# ESP32_WITH_USBCV1I1.net
KiCad netlist of a schematic drawn in Altium Designer
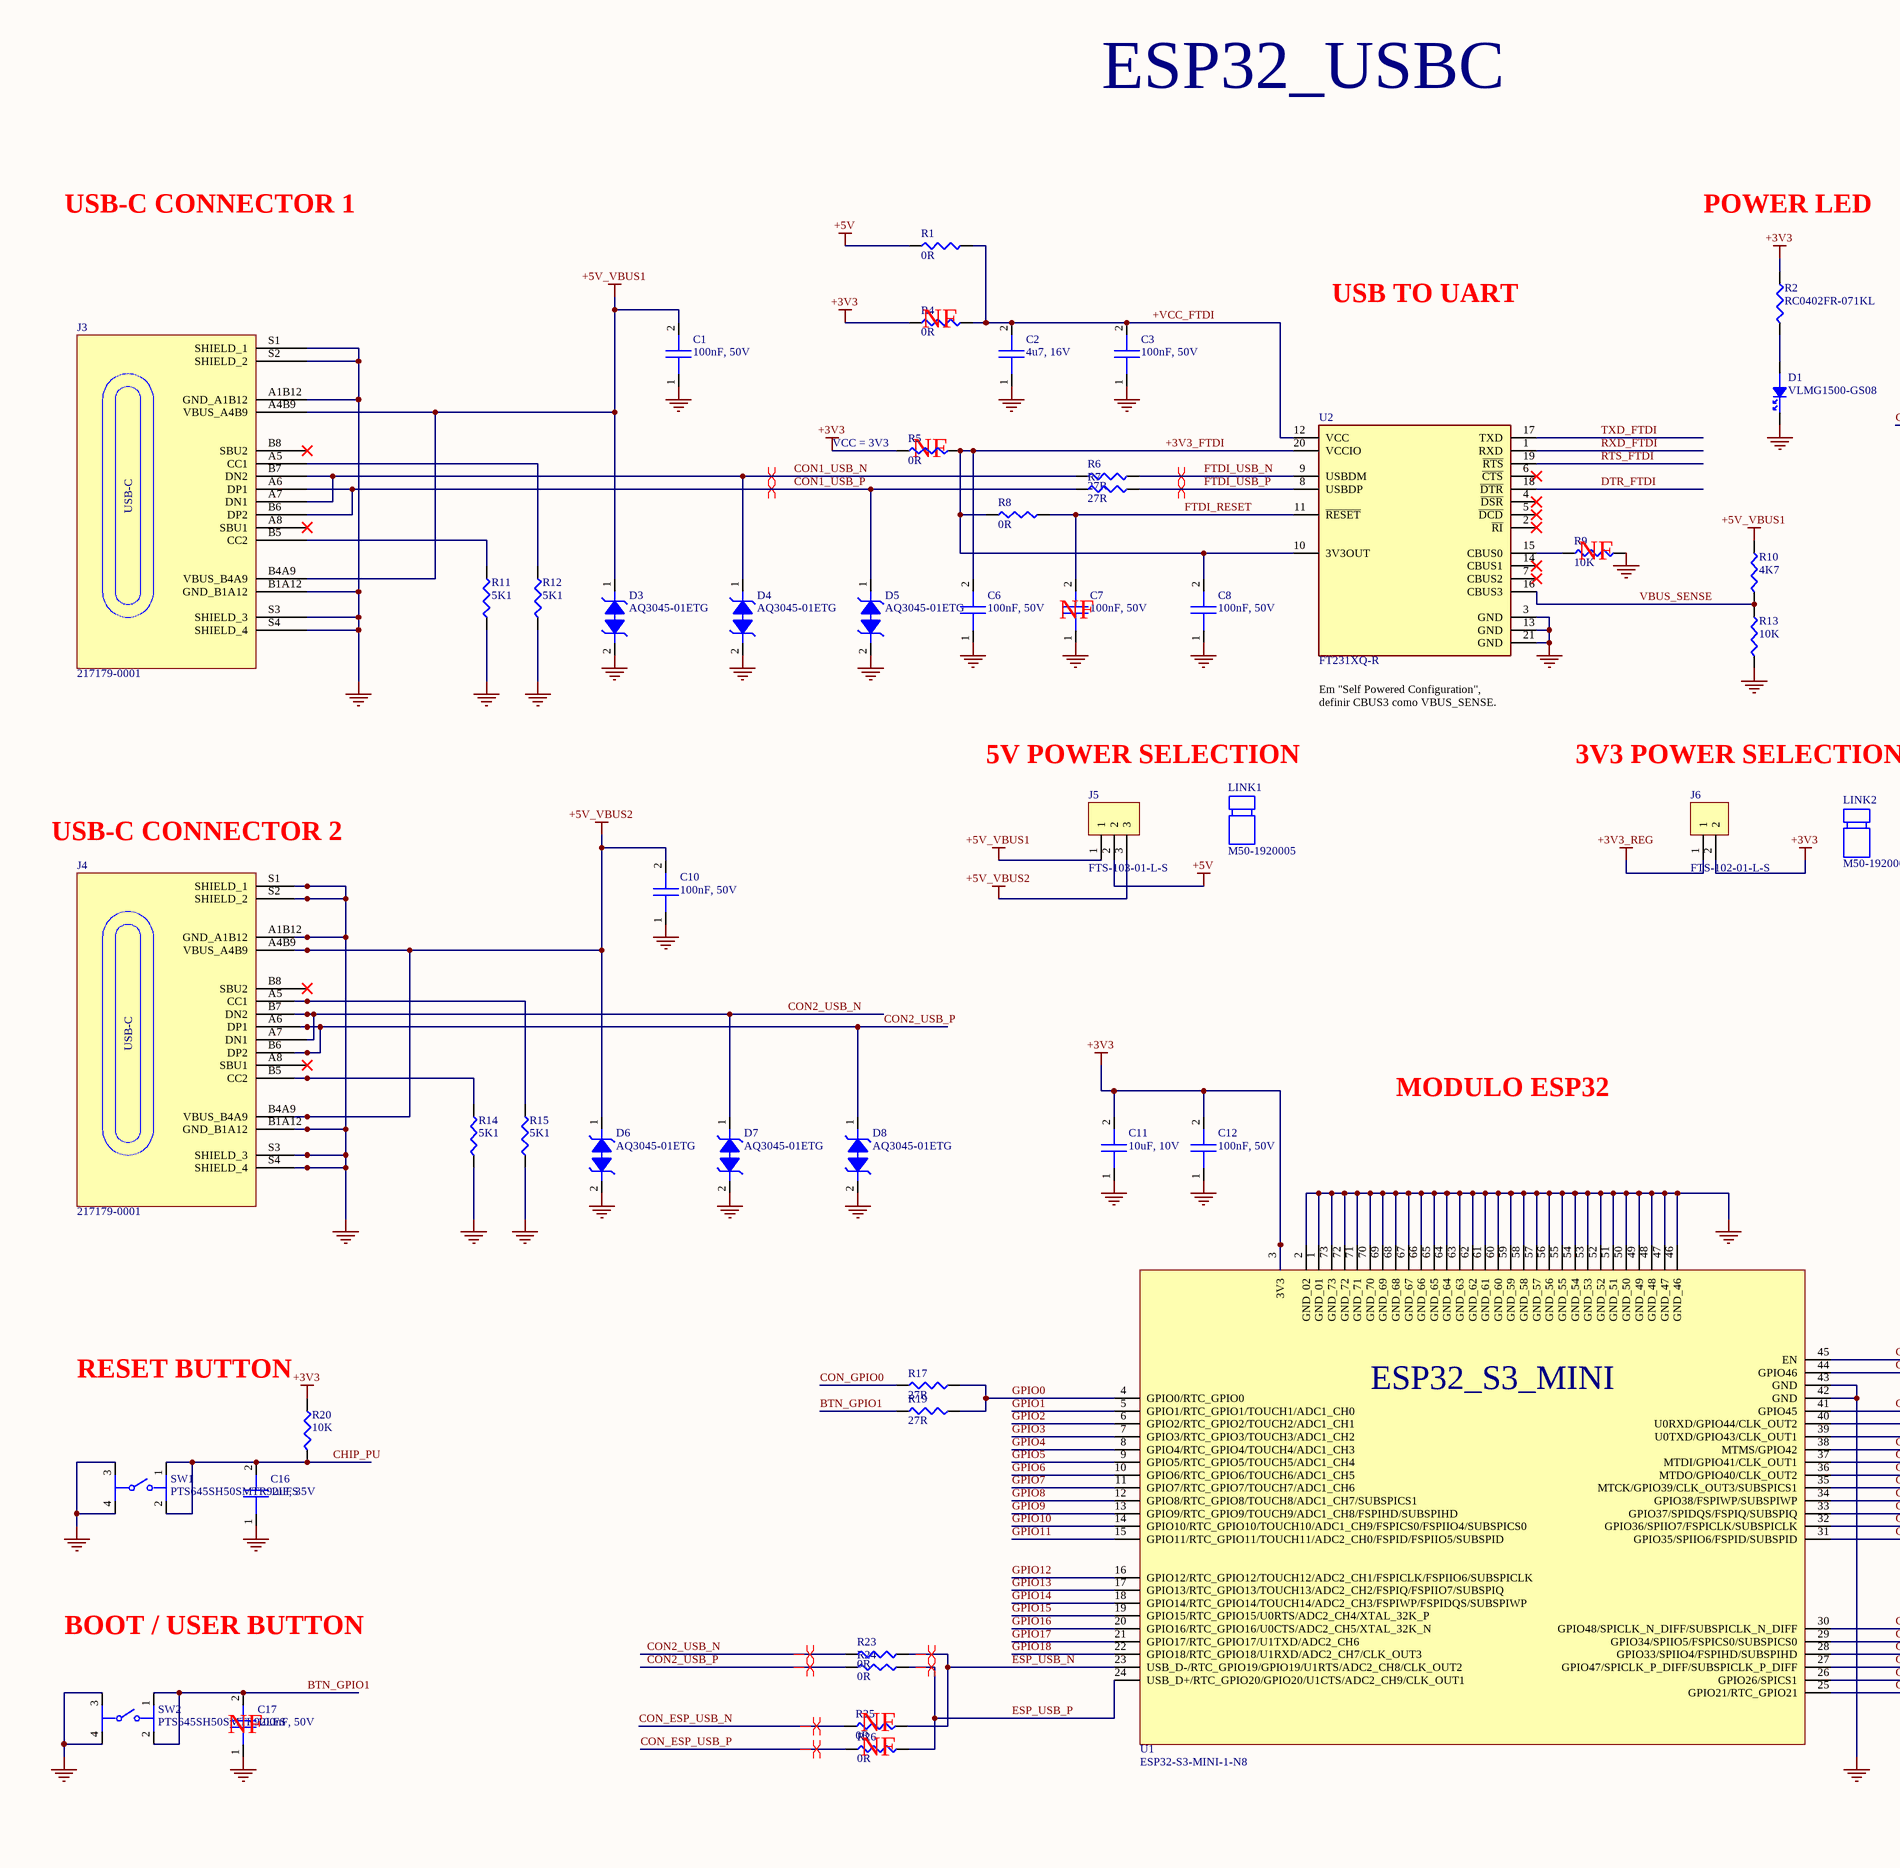
[diagram p0: ESP32_WITH_USBCV1I1.SchDoc, left]
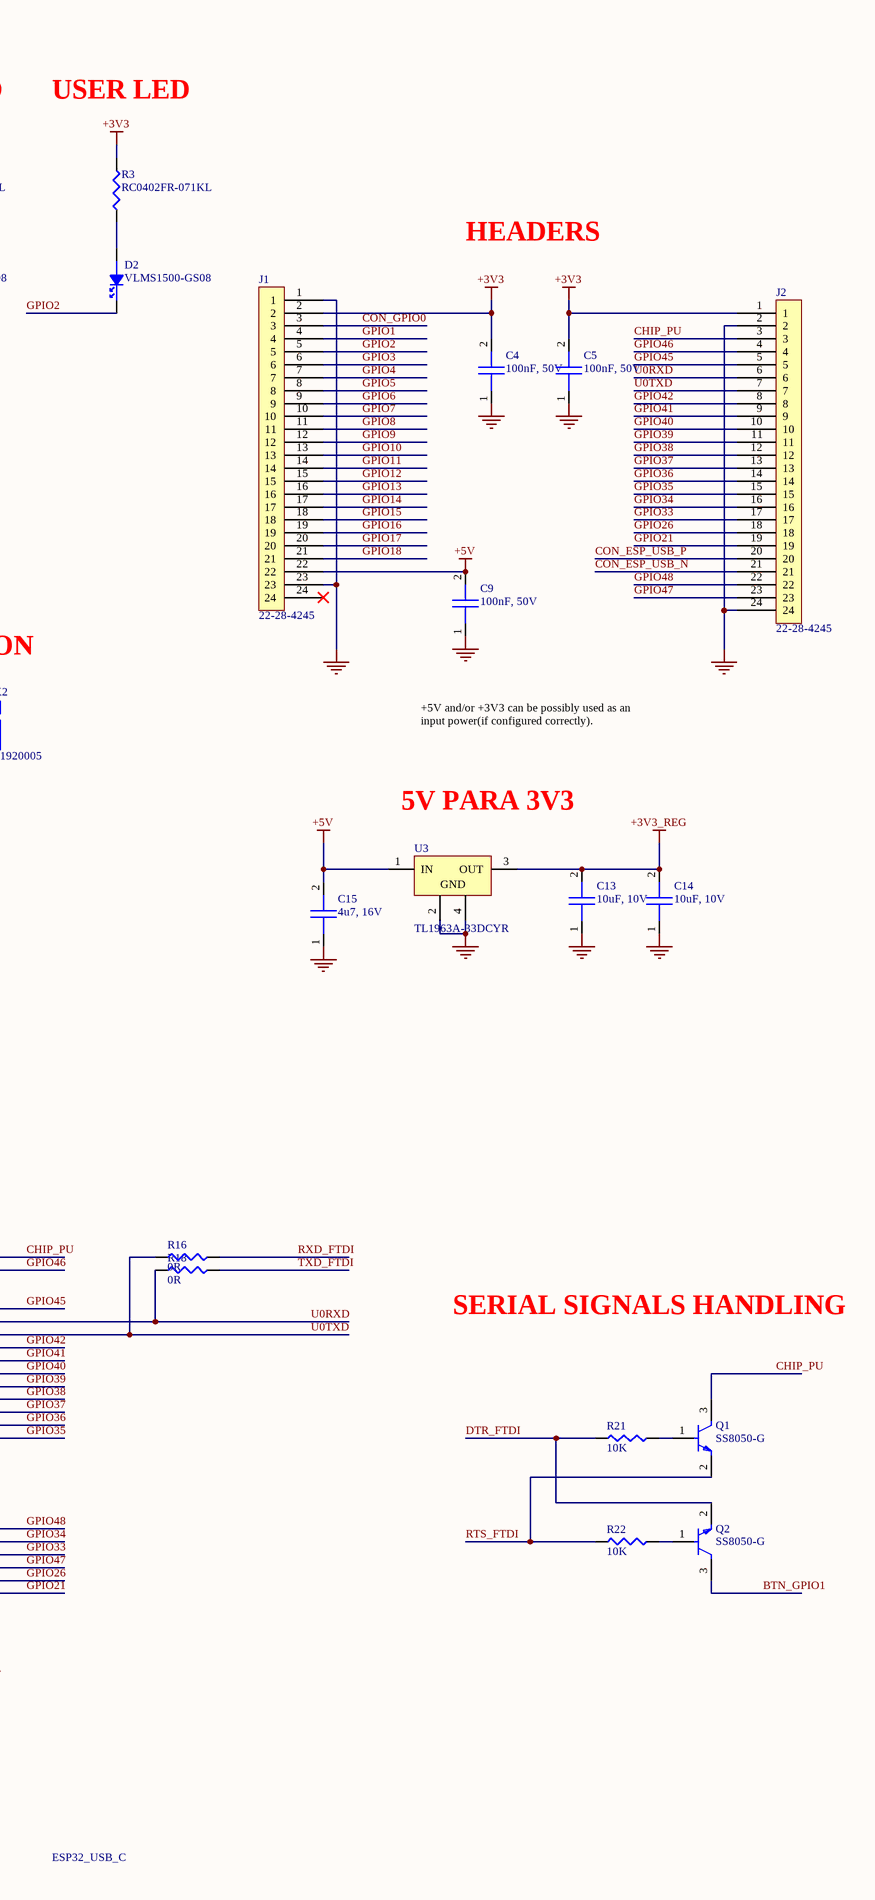
[diagram p1: ESP32_WITH_USBCV1I1.SchDoc, right]

(export (version "E")
  (design (tool "Eeschema 10.0.6"))
  (components
    (comp (ref "C1")
      (value "100nF, 50V")
      (footprint "CAPC1005X70N")
      (description "CAP CER 0.1UF 50V X7R 0402")
      (fields
        (field (name "MANUFACTURER") "Samsung")
        (field (name "MANUFACTURER PART NUMBER") "CL05B104KB54PNC")
      )
      (libsource (lib "Schlib") (part "CL05B104KB54PNC"))
    )
    (comp (ref "C2")
      (value "4u7, 16V")
      (footprint "CAPC1005X70N")
      (description "CAP CER 4.7UF 16V X5R 0402")
      (fields
        (field (name "MANUFACTURER") "Samsung")
        (field (name "MANUFACTURER PART NUMBER") "CL05A475MO5NUNC")
      )
      (libsource (lib "Schlib") (part "CL05A475MO5NUNC"))
    )
    (comp (ref "C3")
      (value "100nF, 50V")
      (footprint "CAPC1005X70N")
      (description "CAP CER 0.1UF 50V X7R 0402")
      (fields
        (field (name "MANUFACTURER") "Samsung")
        (field (name "MANUFACTURER PART NUMBER") "CL05B104KB54PNC")
      )
      (libsource (lib "Schlib") (part "CL05B104KB54PNC"))
    )
    (comp (ref "C4")
      (value "100nF, 50V")
      (footprint "CAPC1005X70N")
      (description "CAP CER 0.1UF 50V X7R 0402")
      (fields
        (field (name "MANUFACTURER") "Samsung")
        (field (name "MANUFACTURER PART NUMBER") "CL05B104KB54PNC")
      )
      (libsource (lib "Schlib") (part "CL05B104KB54PNC"))
    )
    (comp (ref "C5")
      (value "100nF, 50V")
      (footprint "CAPC1005X70N")
      (description "CAP CER 0.1UF 50V X7R 0402")
      (fields
        (field (name "MANUFACTURER") "Samsung")
        (field (name "MANUFACTURER PART NUMBER") "CL05B104KB54PNC")
      )
      (libsource (lib "Schlib") (part "CL05B104KB54PNC"))
    )
    (comp (ref "C6")
      (value "100nF, 50V")
      (footprint "CAPC1005X70N")
      (description "CAP CER 0.1UF 50V X7R 0402")
      (fields
        (field (name "MANUFACTURER") "Samsung")
        (field (name "MANUFACTURER PART NUMBER") "CL05B104KB54PNC")
      )
      (libsource (lib "Schlib") (part "CL05B104KB54PNC"))
    )
    (comp (ref "C7")
      (value "100nF, 50V")
      (footprint "CAPC1005X70N")
      (description "CAP CER 0.1UF 50V X7R 0402")
      (fields
        (field (name "MANUFACTURER") "Samsung")
        (field (name "MANUFACTURER PART NUMBER") "CL05B104KB54PNC")
      )
      (libsource (lib "Schlib") (part "CL05B104KB54PNC"))
    )
    (comp (ref "C8")
      (value "100nF, 50V")
      (footprint "CAPC1005X70N")
      (description "CAP CER 0.1UF 50V X7R 0402")
      (fields
        (field (name "MANUFACTURER") "Samsung")
        (field (name "MANUFACTURER PART NUMBER") "CL05B104KB54PNC")
      )
      (libsource (lib "Schlib") (part "CL05B104KB54PNC"))
    )
    (comp (ref "C9")
      (value "100nF, 50V")
      (footprint "CAPC1005X70N")
      (description "CAP CER 0.1UF 50V X7R 0402")
      (fields
        (field (name "MANUFACTURER") "Samsung")
        (field (name "MANUFACTURER PART NUMBER") "CL05B104KB54PNC")
      )
      (libsource (lib "Schlib") (part "CL05B104KB54PNC"))
    )
    (comp (ref "C10")
      (value "100nF, 50V")
      (footprint "CAPC1005X70N")
      (description "CAP CER 0.1UF 50V X7R 0402")
      (fields
        (field (name "MANUFACTURER") "Samsung")
        (field (name "MANUFACTURER PART NUMBER") "CL05B104KB54PNC")
      )
      (libsource (lib "Schlib") (part "CL05B104KB54PNC"))
    )
    (comp (ref "C11")
      (value "10uF, 10V")
      (footprint "CAPC1005X70N")
      (description "CAP CER 10UF 10V X5R 0402")
      (fields
        (field (name "MANUFACTURER") "Samsung")
        (field (name "MANUFACTURER PART NUMBER") "CL05A106MP8NUB8")
      )
      (libsource (lib "Schlib") (part "CL05A106MP8NUB8"))
    )
    (comp (ref "C12")
      (value "100nF, 50V")
      (footprint "CAPC1005X70N")
      (description "CAP CER 0.1UF 50V X7R 0402")
      (fields
        (field (name "MANUFACTURER") "Samsung")
        (field (name "MANUFACTURER PART NUMBER") "CL05B104KB54PNC")
      )
      (libsource (lib "Schlib") (part "CL05B104KB54PNC"))
    )
    (comp (ref "C13")
      (value "10uF, 10V")
      (footprint "CAPC1005X70N")
      (description "CAP CER 10UF 10V X5R 0402")
      (fields
        (field (name "MANUFACTURER") "Samsung")
        (field (name "MANUFACTURER PART NUMBER") "CL05A106MP8NUB8")
      )
      (libsource (lib "Schlib") (part "CL05A106MP8NUB8"))
    )
    (comp (ref "C14")
      (value "10uF, 10V")
      (footprint "CAPC1005X70N")
      (description "CAP CER 10UF 10V X5R 0402")
      (fields
        (field (name "MANUFACTURER") "Samsung")
        (field (name "MANUFACTURER PART NUMBER") "CL05A106MP8NUB8")
      )
      (libsource (lib "Schlib") (part "CL05A106MP8NUB8"))
    )
    (comp (ref "C15")
      (value "4u7, 16V")
      (footprint "CAPC1005X70N")
      (description "CAP CER 4.7UF 16V X5R 0402")
      (fields
        (field (name "MANUFACTURER") "Samsung")
        (field (name "MANUFACTURER PART NUMBER") "CL05A475MO5NUNC")
      )
      (libsource (lib "Schlib") (part "CL05A475MO5NUNC"))
    )
    (comp (ref "C16")
      (value "1uF, 35V")
      (footprint "CAPC1005X70N")
      (description "1 µF ±10% 35V Ceramic Capacitor X5R 0402")
      (fields
        (field (name "MANUFACTURER") "Samsung")
        (field (name "MANUFACTURER PART NUMBER") "CL05A105KL5NRNC")
      )
      (libsource (lib "Schlib") (part "CL05A105KL5NRNC"))
    )
    (comp (ref "C17")
      (value "100nF, 50V")
      (footprint "CAPC1005X70N")
      (description "CAP CER 0.1UF 50V X7R 0402")
      (fields
        (field (name "MANUFACTURER") "Samsung")
        (field (name "MANUFACTURER PART NUMBER") "CL05B104KB54PNC")
      )
      (libsource (lib "Schlib") (part "CL05B104KB54PNC"))
    )
    (comp (ref "D1")
      (value "VLMG1500-GS08")
      (footprint "LEDO4O2G")
      (description "LED YLW-GRN 0402 SMD")
      (fields (field (name "MANUFACTURER") "Vishay") (field (name "LCSC PART NUMBER") "C511404"))
      (libsource (lib "Schlib") (part "VLMG1500-GS08"))
    )
    (comp (ref "D2")
      (value "VLMS1500-GS08")
      (footprint "LEDO4O2R")
      (description "Single Color LED, Super Red, 0.5mm")
      (fields (field (name "MANUFACTURER") "Vishay") (field (name "LCSC PART NUMBER") "C511370"))
      (libsource (lib "Schlib") (part "VLMS1500-GS08"))
    )
    (comp (ref "D3")
      (value "AQ3045-01ETG")
      (footprint "SOD882")
      (description "TVS DIODE 5.3VWM 12VC SOD882")
      (fields (field (name "MANUFACTURER") "Littelfuse") (field (name "LCSC PART NUMBER") "C3710326"))
      (libsource (lib "Schlib") (part "AQ3045-01ETG"))
    )
    (comp (ref "D4")
      (value "AQ3045-01ETG")
      (footprint "SOD882")
      (description "TVS DIODE 5.3VWM 12VC SOD882")
      (fields (field (name "MANUFACTURER") "Littelfuse") (field (name "LCSC PART NUMBER") "C3710326"))
      (libsource (lib "Schlib") (part "AQ3045-01ETG"))
    )
    (comp (ref "D5")
      (value "AQ3045-01ETG")
      (footprint "SOD882")
      (description "TVS DIODE 5.3VWM 12VC SOD882")
      (fields (field (name "MANUFACTURER") "Littelfuse") (field (name "LCSC PART NUMBER") "C3710326"))
      (libsource (lib "Schlib") (part "AQ3045-01ETG"))
    )
    (comp (ref "D6")
      (value "AQ3045-01ETG")
      (footprint "SOD882")
      (description "TVS DIODE 5.3VWM 12VC SOD882")
      (fields (field (name "MANUFACTURER") "Littelfuse") (field (name "LCSC PART NUMBER") "C3710326"))
      (libsource (lib "Schlib") (part "AQ3045-01ETG"))
    )
    (comp (ref "D7")
      (value "AQ3045-01ETG")
      (footprint "SOD882")
      (description "TVS DIODE 5.3VWM 12VC SOD882")
      (fields (field (name "MANUFACTURER") "Littelfuse") (field (name "LCSC PART NUMBER") "C3710326"))
      (libsource (lib "Schlib") (part "AQ3045-01ETG"))
    )
    (comp (ref "D8")
      (value "AQ3045-01ETG")
      (footprint "SOD882")
      (description "TVS DIODE 5.3VWM 12VC SOD882")
      (fields (field (name "MANUFACTURER") "Littelfuse") (field (name "LCSC PART NUMBER") "C3710326"))
      (libsource (lib "Schlib") (part "AQ3045-01ETG"))
    )
    (comp (ref "J1")
      (value "22-28-4245")
      (footprint "HDR_1X24_2.54MM")
      (description "CONN HEADER VERT 24POS 2.54MM")
      (fields (field (name "MANUFACTURER") "Molex") (field (name "LCSC PART NUMBER") "C7145888"))
      (libsource (lib "") (part "22-28-4245_1"))
    )
    (comp (ref "J2")
      (value "22-28-4245")
      (footprint "HDR_1X24_2.54MM")
      (description "CONN HEADER VERT 24POS 2.54MM")
      (fields (field (name "MANUFACTURER") "Molex") (field (name "LCSC PART NUMBER") "C7145888"))
      (libsource (lib "Schlib") (part "22-28-4245"))
    )
    (comp (ref "J3")
      (value "217179-0001")
      (footprint "FP-2171790001-MFG")
      (description "CONN RCP USB2.0 TYP C 24P SMD RA")
      (fields (field (name "MANUFACTURER") "Molex") (field (name "LCSC PART NUMBER") "C3197684"))
      (libsource (lib "Schlib") (part "217179-0001"))
    )
    (comp (ref "J4")
      (value "217179-0001")
      (footprint "FP-2171790001-MFG")
      (description "CONN RCP USB2.0 TYP C 24P SMD RA")
      (fields (field (name "MANUFACTURER") "Molex") (field (name "LCSC PART NUMBER") "C3197684"))
      (libsource (lib "Schlib") (part "217179-0001"))
    )
    (comp (ref "J5")
      (value "FTS-103-01-L-S")
      (footprint "HDR_1X3_1.27MM")
      (description "CONN HEADER VERT 3POS 1.27MM")
      (fields (field (name "MANUFACTURER") "Samtec") (field (name "LCSC PART NUMBER") "C6253705"))
      (libsource (lib "Schlib") (part "FTS-103-01-L-S"))
    )
    (comp (ref "J6")
      (value "FTS-102-01-L-S")
      (footprint "HDR_1X2_1.27MM")
      (description "CONN HEADER VERT 2POS 1.27MM")
      (fields (field (name "MANUFACTURER") "Samtec") (field (name "LCSC PART NUMBER") "C7194937"))
      (libsource (lib "Schlib") (part "FTS-102-01-L-S"))
    )
    (comp (ref "LINK1")
      (value "M50-1920005")
      (description "CONN SHUNT 1.27MM RED")
      (fields (field (name "MANUFACTURER") "Harwin") (field (name "LCSC PART NUMBER") "C6985646"))
      (libsource (lib "Schlib") (part "M50-1920005"))
    )
    (comp (ref "LINK2")
      (value "M50-1920005")
      (description "CONN SHUNT 1.27MM RED")
      (fields (field (name "MANUFACTURER") "Harwin") (field (name "LCSC PART NUMBER") "C6985646"))
      (libsource (lib "Schlib") (part "M50-1920005"))
    )
    (comp (ref "Q1")
      (value "SS8050-G")
      (footprint "FP-SS8050-G-IPC_B")
      (description "TRANS NPN 25V 1.5A SOT-23-3")
      (fields (field (name "MANUFACTURER") "Comchip") (field (name "LCSC PART NUMBER") "C164886"))
      (libsource (lib "Schlib") (part "SS8050-G"))
    )
    (comp (ref "Q2")
      (value "SS8050-G")
      (footprint "FP-SS8050-G-IPC_B")
      (description "TRANS NPN 25V 1.5A SOT-23-3")
      (fields (field (name "MANUFACTURER") "Comchip") (field (name "LCSC PART NUMBER") "C164886"))
      (libsource (lib "Schlib") (part "SS8050-G"))
    )
    (comp (ref "R1")
      (value "0R")
      (footprint "RESC1005X37N")
      (description "RES SMD 0 OHM JUMPER 1/16W 0402")
      (fields
        (field (name "MANUFACTURER") "Yageo")
        (field (name "MANUFACTURER PART NUMBER") "AC0402JR-070RL")
      )
      (libsource (lib "Schlib") (part "AC0402JR-070RL"))
    )
    (comp (ref "R2")
      (value "RC0402FR-071KL")
      (footprint "RESC1005X37N")
      (description "RES 1K OHM 1% 1/16W 0402")
      (fields (field (name "MANUFACTURER") "Yageo") (field (name "TOLERANCE") "1%"))
      (libsource (lib "Schlib") (part "RC0402FR-071KL"))
    )
    (comp (ref "R3")
      (value "RC0402FR-071KL")
      (footprint "RESC1005X37N")
      (description "RES 1K OHM 1% 1/16W 0402")
      (fields (field (name "MANUFACTURER") "Yageo") (field (name "TOLERANCE") "1%"))
      (libsource (lib "Schlib") (part "RC0402FR-071KL"))
    )
    (comp (ref "R4")
      (value "0R")
      (footprint "RESC1005X37N")
      (description "RES SMD 0 OHM JUMPER 1/16W 0402")
      (fields
        (field (name "MANUFACTURER") "Yageo")
        (field (name "MANUFACTURER PART NUMBER") "AC0402JR-070RL")
      )
      (libsource (lib "Schlib") (part "AC0402JR-070RL"))
    )
    (comp (ref "R5")
      (value "0R")
      (footprint "RESC1005X37N")
      (description "RES SMD 0 OHM JUMPER 1/16W 0402")
      (fields
        (field (name "MANUFACTURER") "Yageo")
        (field (name "MANUFACTURER PART NUMBER") "AC0402JR-070RL")
      )
      (libsource (lib "Schlib") (part "AC0402JR-070RL"))
    )
    (comp (ref "R6")
      (value "27R")
      (footprint "RESC1005X37N")
      (description "RES 27 OHM 1% 1/16W 0402")
      (fields
        (field (name "MANUFACTURER") "Yageo")
        (field (name "MANUFACTURER PART NUMBER") "RC0402FR-0727RL")
      )
      (libsource (lib "Schlib") (part "RC0402FR-0727RL"))
    )
    (comp (ref "R7")
      (value "27R")
      (footprint "RESC1005X37N")
      (description "RES 27 OHM 1% 1/16W 0402")
      (fields
        (field (name "MANUFACTURER") "Yageo")
        (field (name "MANUFACTURER PART NUMBER") "RC0402FR-0727RL")
      )
      (libsource (lib "Schlib") (part "RC0402FR-0727RL"))
    )
    (comp (ref "R8")
      (value "0R")
      (footprint "RESC1005X37N")
      (description "RES SMD 0 OHM JUMPER 1/16W 0402")
      (fields
        (field (name "MANUFACTURER") "Yageo")
        (field (name "MANUFACTURER PART NUMBER") "AC0402JR-070RL")
      )
      (libsource (lib "Schlib") (part "AC0402JR-070RL"))
    )
    (comp (ref "R9")
      (value "10K")
      (footprint "RESC1005X37N")
      (description "RES SMD 10K OHM 1% 1/16W 0402")
      (fields
        (field (name "MANUFACTURER") "Yageo")
        (field (name "MANUFACTURER PART NUMBER") "AC0402FR-0710KL")
      )
      (libsource (lib "Schlib") (part "AC0402FR-0710KL"))
    )
    (comp (ref "R10")
      (value "4K7")
      (footprint "RESC1005X37N")
      (description "RES 4.7K OHM 1% 1/16W 0402")
      (fields
        (field (name "MANUFACTURER") "Yageo")
        (field (name "MANUFACTURER PART NUMBER") "RC0402FR-074K7L")
      )
      (libsource (lib "Schlib") (part "RC0402FR-074K7L"))
    )
    (comp (ref "R11")
      (value "5K1")
      (footprint "RESC1005X37N")
      (description "RES SMD 5.1K OHM 1% 1/16W 0402")
      (fields
        (field (name "MANUFACTURER") "Yageo")
        (field (name "MANUFACTURER PART NUMBER") "AC0402FR-075K1L")
      )
      (libsource (lib "Schlib") (part "AC0402FR-075K1L"))
    )
    (comp (ref "R12")
      (value "5K1")
      (footprint "RESC1005X37N")
      (description "RES SMD 5.1K OHM 1% 1/16W 0402")
      (fields
        (field (name "MANUFACTURER") "Yageo")
        (field (name "MANUFACTURER PART NUMBER") "AC0402FR-075K1L")
      )
      (libsource (lib "Schlib") (part "AC0402FR-075K1L"))
    )
    (comp (ref "R13")
      (value "10K")
      (footprint "RESC1005X37N")
      (description "RES SMD 10K OHM 1% 1/16W 0402")
      (fields
        (field (name "MANUFACTURER") "Yageo")
        (field (name "MANUFACTURER PART NUMBER") "AC0402FR-0710KL")
      )
      (libsource (lib "Schlib") (part "AC0402FR-0710KL"))
    )
    (comp (ref "R14")
      (value "5K1")
      (footprint "RESC1005X37N")
      (description "RES SMD 5.1K OHM 1% 1/16W 0402")
      (fields
        (field (name "MANUFACTURER") "Yageo")
        (field (name "MANUFACTURER PART NUMBER") "AC0402FR-075K1L")
      )
      (libsource (lib "Schlib") (part "AC0402FR-075K1L"))
    )
    (comp (ref "R15")
      (value "5K1")
      (footprint "RESC1005X37N")
      (description "RES SMD 5.1K OHM 1% 1/16W 0402")
      (fields
        (field (name "MANUFACTURER") "Yageo")
        (field (name "MANUFACTURER PART NUMBER") "AC0402FR-075K1L")
      )
      (libsource (lib "Schlib") (part "AC0402FR-075K1L"))
    )
    (comp (ref "R16")
      (value "0R")
      (footprint "RESC1005X37N")
      (description "RES SMD 0 OHM JUMPER 1/16W 0402")
      (fields
        (field (name "MANUFACTURER") "Yageo")
        (field (name "MANUFACTURER PART NUMBER") "AC0402JR-070RL")
      )
      (libsource (lib "Schlib") (part "AC0402JR-070RL"))
    )
    (comp (ref "R17")
      (value "27R")
      (footprint "RESC1005X37N")
      (description "RES 27 OHM 1% 1/16W 0402")
      (fields
        (field (name "MANUFACTURER") "Yageo")
        (field (name "MANUFACTURER PART NUMBER") "RC0402FR-0727RL")
      )
      (libsource (lib "Schlib") (part "RC0402FR-0727RL"))
    )
    (comp (ref "R18")
      (value "0R")
      (footprint "RESC1005X37N")
      (description "RES SMD 0 OHM JUMPER 1/16W 0402")
      (fields
        (field (name "MANUFACTURER") "Yageo")
        (field (name "MANUFACTURER PART NUMBER") "AC0402JR-070RL")
      )
      (libsource (lib "Schlib") (part "AC0402JR-070RL"))
    )
    (comp (ref "R19")
      (value "27R")
      (footprint "RESC1005X37N")
      (description "RES 27 OHM 1% 1/16W 0402")
      (fields
        (field (name "MANUFACTURER") "Yageo")
        (field (name "MANUFACTURER PART NUMBER") "RC0402FR-0727RL")
      )
      (libsource (lib "Schlib") (part "RC0402FR-0727RL"))
    )
    (comp (ref "R20")
      (value "10K")
      (footprint "RESC1005X37N")
      (description "RES SMD 10K OHM 1% 1/16W 0402")
      (fields
        (field (name "MANUFACTURER") "Yageo")
        (field (name "MANUFACTURER PART NUMBER") "AC0402FR-0710KL")
      )
      (libsource (lib "Schlib") (part "AC0402FR-0710KL"))
    )
    (comp (ref "R21")
      (value "10K")
      (footprint "RESC1005X37N")
      (description "RES SMD 10K OHM 1% 1/16W 0402")
      (fields
        (field (name "MANUFACTURER") "Yageo")
        (field (name "MANUFACTURER PART NUMBER") "AC0402FR-0710KL")
      )
      (libsource (lib "Schlib") (part "AC0402FR-0710KL"))
    )
    (comp (ref "R22")
      (value "10K")
      (footprint "RESC1005X37N")
      (description "RES SMD 10K OHM 1% 1/16W 0402")
      (fields
        (field (name "MANUFACTURER") "Yageo")
        (field (name "MANUFACTURER PART NUMBER") "AC0402FR-0710KL")
      )
      (libsource (lib "Schlib") (part "AC0402FR-0710KL"))
    )
    (comp (ref "R23")
      (value "0R")
      (footprint "RESC1005X37N")
      (description "RES SMD 0 OHM JUMPER 1/16W 0402")
      (fields
        (field (name "MANUFACTURER") "Yageo")
        (field (name "MANUFACTURER PART NUMBER") "AC0402JR-070RL")
      )
      (libsource (lib "Schlib") (part "AC0402JR-070RL"))
    )
    (comp (ref "R24")
      (value "0R")
      (footprint "RESC1005X37N")
      (description "RES SMD 0 OHM JUMPER 1/16W 0402")
      (fields
        (field (name "MANUFACTURER") "Yageo")
        (field (name "MANUFACTURER PART NUMBER") "AC0402JR-070RL")
      )
      (libsource (lib "Schlib") (part "AC0402JR-070RL"))
    )
    (comp (ref "R25")
      (value "0R")
      (footprint "RESC1005X37N")
      (description "RES SMD 0 OHM JUMPER 1/16W 0402")
      (fields
        (field (name "MANUFACTURER") "Yageo")
        (field (name "MANUFACTURER PART NUMBER") "AC0402JR-070RL")
      )
      (libsource (lib "Schlib") (part "AC0402JR-070RL"))
    )
    (comp (ref "R26")
      (value "0R")
      (footprint "RESC1005X37N")
      (description "RES SMD 0 OHM JUMPER 1/16W 0402")
      (fields
        (field (name "MANUFACTURER") "Yageo")
        (field (name "MANUFACTURER PART NUMBER") "AC0402JR-070RL")
      )
      (libsource (lib "Schlib") (part "AC0402JR-070RL"))
    )
    (comp (ref "SW1")
      (value "PTS645SH50SMTR92LFS")
      (footprint "FP-PTS645SH50SMTR92LFS-MFG")
      (description "SWITCH TACTILE SPST-NO 0.05A 12V")
      (fields (field (name "MANUFACTURER") "ITT C&K") (field (name "LCSC PART NUMBER") "C221869"))
      (libsource (lib "Schlib") (part "PTS645SH50SMTR92LFS"))
    )
    (comp (ref "SW2")
      (value "PTS645SH50SMTR92LFS")
      (footprint "FP-PTS645SH50SMTR92LFS-MFG")
      (description "SWITCH TACTILE SPST-NO 0.05A 12V")
      (fields (field (name "MANUFACTURER") "ITT C&K") (field (name "LCSC PART NUMBER") "C221869"))
      (libsource (lib "Schlib") (part "PTS645SH50SMTR92LFS"))
    )
    (comp (ref "U1")
      (value "ESP32-S3-MINI-1-N8")
      (footprint "XCVR_ESP32-S3-MINI-1-N8")
      (description "SMD module, ESP32-S3FN8, 8 MB SPI flash, PCB antenna")
      (fields (field (name "MANUFACTURER") "Espressif Systems") (field (name "LCSC PART NUMBER") "C2913206"))
      (libsource (lib "Schlib") (part "ESP32-S3-MINI-1-N8"))
    )
    (comp (ref "U2")
      (value "FT231XQ-R")
      (footprint "FP-QFN-20-IPC_B")
      (description "IC USB SERIAL FULL UART 20QFN")
      (fields (field (name "MANUFACTURER") "FTDI") (field (name "LCSC PART NUMBER") "C132159"))
      (libsource (lib "Schlib") (part "FT231XQ-R"))
    )
    (comp (ref "U3")
      (value "TL1963A-33DCYR")
      (footprint "DCY0004A_N")
      (description "IC REG LIN 3.3V 1.5A SOT-223-4")
      (fields (field (name "MANUFACTURER") "Texas Instruments") (field (name "LCSC PART NUMBER") "C181262"))
      (libsource (lib "Schlib") (part "TL1963A-33DCYR"))
    )
  )
  (nets
    (net (code "1") (name "+3V3") (class "Default")
      (node (ref "C11") (pin "2") (pinfunction "2_2") (pintype "passive"))
      (node (ref "C12") (pin "2") (pinfunction "2_2") (pintype "passive"))
      (node (ref "C4") (pin "2") (pinfunction "2_2") (pintype "passive"))
      (node (ref "C5") (pin "2") (pinfunction "2_2") (pintype "passive"))
      (node (ref "J1") (pin "2") (pinfunction "2_2") (pintype "passive"))
      (node (ref "J2") (pin "1") (pinfunction "1_1") (pintype "passive"))
      (node (ref "J6") (pin "2") (pinfunction "2_2") (pintype "passive"))
      (node (ref "R2") (pin "2") (pinfunction "2_2") (pintype "passive"))
      (node (ref "R20") (pin "2") (pinfunction "2_2") (pintype "passive"))
      (node (ref "R3") (pin "2") (pinfunction "2_2") (pintype "passive"))
      (node (ref "R4") (pin "1") (pinfunction "1_1") (pintype "passive"))
      (node (ref "R5") (pin "1") (pinfunction "1_1") (pintype "passive"))
      (node (ref "U1") (pin "3") (pinfunction "3V3_3") (pintype "passive"))
    )
    (net (code "2") (name "+3V3_REG") (class "Default")
      (node (ref "C13") (pin "2") (pinfunction "2_2") (pintype "passive"))
      (node (ref "C14") (pin "2") (pinfunction "2_2") (pintype "passive"))
      (node (ref "J6") (pin "1") (pinfunction "1_1") (pintype "passive"))
      (node (ref "U3") (pin "3") (pinfunction "OUT_3") (pintype "power_in"))
    )
    (net (code "3") (name "+5V") (class "Default")
      (node (ref "C15") (pin "2") (pinfunction "2_2") (pintype "passive"))
      (node (ref "C9") (pin "2") (pinfunction "2_2") (pintype "passive"))
      (node (ref "J1") (pin "22") (pinfunction "22_22") (pintype "passive"))
      (node (ref "J5") (pin "2") (pinfunction "2_2") (pintype "passive"))
      (node (ref "R1") (pin "1") (pinfunction "1_1") (pintype "passive"))
      (node (ref "U3") (pin "1") (pinfunction "IN_1") (pintype "power_in"))
    )
    (net (code "4") (name "+5V_VBUS1") (class "Default")
      (node (ref "C1") (pin "2") (pinfunction "2_2") (pintype "passive"))
      (node (ref "D3") (pin "1") (pinfunction "1_1") (pintype "passive"))
      (node (ref "J3") (pin "A4B9") (pinfunction "VBUS_A4B9_A4B9") (pintype "passive"))
      (node (ref "J3") (pin "B4A9") (pinfunction "VBUS_B4A9_B4A9") (pintype "passive"))
      (node (ref "J5") (pin "1") (pinfunction "1_1") (pintype "passive"))
      (node (ref "R10") (pin "2") (pinfunction "2_2") (pintype "passive"))
    )
    (net (code "5") (name "+5V_VBUS2") (class "Default")
      (node (ref "C10") (pin "2") (pinfunction "2_2") (pintype "passive"))
      (node (ref "D6") (pin "1") (pinfunction "1_1") (pintype "passive"))
      (node (ref "J4") (pin "A4B9") (pinfunction "VBUS_A4B9_A4B9") (pintype "passive"))
      (node (ref "J4") (pin "B4A9") (pinfunction "VBUS_B4A9_B4A9") (pintype "passive"))
      (node (ref "J5") (pin "3") (pinfunction "3_3") (pintype "passive"))
    )
    (net (code "6") (name "/+3V3_FTDI") (class "Default")
      (node (ref "C6") (pin "2") (pinfunction "2_2") (pintype "passive"))
      (node (ref "C8") (pin "2") (pinfunction "2_2") (pintype "passive"))
      (node (ref "R5") (pin "2") (pinfunction "2_2") (pintype "passive"))
      (node (ref "R8") (pin "1") (pinfunction "1_1") (pintype "passive"))
      (node (ref "U2") (pin "10") (pinfunction "3V3OUT_10") (pintype "passive"))
      (node (ref "U2") (pin "20") (pinfunction "VCCIO_20") (pintype "passive"))
    )
    (net (code "7") (name "/+VCC_FTDI") (class "Default")
      (node (ref "C2") (pin "2") (pinfunction "2_2") (pintype "passive"))
      (node (ref "C3") (pin "2") (pinfunction "2_2") (pintype "passive"))
      (node (ref "R1") (pin "2") (pinfunction "2_2") (pintype "passive"))
      (node (ref "R4") (pin "2") (pinfunction "2_2") (pintype "passive"))
      (node (ref "U2") (pin "12") (pinfunction "VCC_12") (pintype "passive"))
    )
    (net (code "8") (name "/BTN_GPIO1") (class "Default")
      (node (ref "C17") (pin "2") (pinfunction "2_2") (pintype "passive"))
      (node (ref "Q2") (pin "3") (pinfunction "C_3") (pintype "passive"))
      (node (ref "R19") (pin "1") (pinfunction "1_1") (pintype "passive"))
      (node (ref "SW2") (pin "1") (pinfunction "1_1") (pintype "passive"))
      (node (ref "SW2") (pin "2") (pinfunction "2_2") (pintype "passive"))
    )
    (net (code "9") (name "/CHIP_PU") (class "Default")
      (node (ref "C16") (pin "2") (pinfunction "2_2") (pintype "passive"))
      (node (ref "J2") (pin "3") (pinfunction "3_3") (pintype "passive"))
      (node (ref "Q1") (pin "3") (pinfunction "C_3") (pintype "passive"))
      (node (ref "R20") (pin "1") (pinfunction "1_1") (pintype "passive"))
      (node (ref "SW1") (pin "1") (pinfunction "1_1") (pintype "passive"))
      (node (ref "SW1") (pin "2") (pinfunction "2_2") (pintype "passive"))
      (node (ref "U1") (pin "45") (pinfunction "EN_45") (pintype "passive"))
    )
    (net (code "10") (name "/CON1_USB_N") (class "Default")
      (node (ref "D4") (pin "1") (pinfunction "1_1") (pintype "passive"))
      (node (ref "J3") (pin "A7") (pinfunction "DN1_A7") (pintype "passive"))
      (node (ref "J3") (pin "B7") (pinfunction "DN2_B7") (pintype "passive"))
      (node (ref "R6") (pin "1") (pinfunction "1_1") (pintype "passive"))
    )
    (net (code "11") (name "/CON1_USB_P") (class "Default")
      (node (ref "D5") (pin "1") (pinfunction "1_1") (pintype "passive"))
      (node (ref "J3") (pin "A6") (pinfunction "DP1_A6") (pintype "passive"))
      (node (ref "J3") (pin "B6") (pinfunction "DP2_B6") (pintype "passive"))
      (node (ref "R7") (pin "1") (pinfunction "1_1") (pintype "passive"))
    )
    (net (code "12") (name "/CON2_USB_N") (class "Default")
      (node (ref "D7") (pin "1") (pinfunction "1_1") (pintype "passive"))
      (node (ref "J4") (pin "A7") (pinfunction "DN1_A7") (pintype "passive"))
      (node (ref "J4") (pin "B7") (pinfunction "DN2_B7") (pintype "passive"))
      (node (ref "R23") (pin "1") (pinfunction "1_1") (pintype "passive"))
    )
    (net (code "13") (name "/CON2_USB_P") (class "Default")
      (node (ref "D8") (pin "1") (pinfunction "1_1") (pintype "passive"))
      (node (ref "J4") (pin "A6") (pinfunction "DP1_A6") (pintype "passive"))
      (node (ref "J4") (pin "B6") (pinfunction "DP2_B6") (pintype "passive"))
      (node (ref "R24") (pin "1") (pinfunction "1_1") (pintype "passive"))
    )
    (net (code "14") (name "/CON_ESP_USB_N") (class "Default")
      (node (ref "J2") (pin "21") (pinfunction "21_21") (pintype "passive"))
      (node (ref "R25") (pin "1") (pinfunction "1_1") (pintype "passive"))
    )
    (net (code "15") (name "/CON_ESP_USB_P") (class "Default")
      (node (ref "J2") (pin "20") (pinfunction "20_20") (pintype "passive"))
      (node (ref "R26") (pin "1") (pinfunction "1_1") (pintype "passive"))
    )
    (net (code "16") (name "/CON_GPIO0") (class "Default")
      (node (ref "J1") (pin "3") (pinfunction "3_3") (pintype "passive"))
      (node (ref "R17") (pin "1") (pinfunction "1_1") (pintype "passive"))
    )
    (net (code "17") (name "/DTR_FTDI") (class "Default")
      (node (ref "Q2") (pin "2") (pinfunction "E_2") (pintype "passive"))
      (node (ref "R21") (pin "2") (pinfunction "2_2") (pintype "passive"))
      (node (ref "U2") (pin "18") (pinfunction "~{DTR}_18") (pintype "passive"))
    )
    (net (code "18") (name "/ESP_USB_N") (class "Default")
      (node (ref "R23") (pin "2") (pinfunction "2_2") (pintype "passive"))
      (node (ref "R25") (pin "2") (pinfunction "2_2") (pintype "passive"))
      (node (ref "U1") (pin "23") (pinfunction "USB_D-/RTC_GPIO19/GPIO19/U1RTS/ADC2_CH8/CLK_OUT2_23") (pintype "passive"))
    )
    (net (code "19") (name "/ESP_USB_P") (class "Default")
      (node (ref "R24") (pin "2") (pinfunction "2_2") (pintype "passive"))
      (node (ref "R26") (pin "2") (pinfunction "2_2") (pintype "passive"))
      (node (ref "U1") (pin "24") (pinfunction "USB_D+/RTC_GPIO20/GPIO20/U1CTS/ADC2_CH9/CLK_OUT1_24") (pintype "passive"))
    )
    (net (code "20") (name "/FTDI_RESET") (class "Default")
      (node (ref "C7") (pin "2") (pinfunction "2_2") (pintype "passive"))
      (node (ref "R8") (pin "2") (pinfunction "2_2") (pintype "passive"))
      (node (ref "U2") (pin "11") (pinfunction "~{RESET}_11") (pintype "passive"))
    )
    (net (code "21") (name "/FTDI_USB_N") (class "Default")
      (node (ref "R6") (pin "2") (pinfunction "2_2") (pintype "passive"))
      (node (ref "U2") (pin "9") (pinfunction "USBDM_9") (pintype "passive"))
    )
    (net (code "22") (name "/FTDI_USB_P") (class "Default")
      (node (ref "R7") (pin "2") (pinfunction "2_2") (pintype "passive"))
      (node (ref "U2") (pin "8") (pinfunction "USBDP_8") (pintype "passive"))
    )
    (net (code "23") (name "/GPIO0") (class "Default")
      (node (ref "R17") (pin "2") (pinfunction "2_2") (pintype "passive"))
      (node (ref "R19") (pin "2") (pinfunction "2_2") (pintype "passive"))
      (node (ref "U1") (pin "4") (pinfunction "GPIO0/RTC_GPIO0_4") (pintype "passive"))
    )
    (net (code "24") (name "/GPIO1") (class "Default")
      (node (ref "J1") (pin "4") (pinfunction "4_4") (pintype "passive"))
      (node (ref "U1") (pin "5") (pinfunction "GPIO1/RTC_GPIO1/TOUCH1/ADC1_CH0_5") (pintype "passive"))
    )
    (net (code "25") (name "/GPIO2") (class "Default")
      (node (ref "D2") (pin "1") (pinfunction "1_1") (pintype "passive"))
      (node (ref "J1") (pin "5") (pinfunction "5_5") (pintype "passive"))
      (node (ref "U1") (pin "6") (pinfunction "GPIO2/RTC_GPIO2/TOUCH2/ADC1_CH1_6") (pintype "passive"))
    )
    (net (code "26") (name "/GPIO3") (class "Default")
      (node (ref "J1") (pin "6") (pinfunction "6_6") (pintype "passive"))
      (node (ref "U1") (pin "7") (pinfunction "GPIO3/RTC_GPIO3/TOUCH3/ADC1_CH2_7") (pintype "passive"))
    )
    (net (code "27") (name "/GPIO4") (class "Default")
      (node (ref "J1") (pin "7") (pinfunction "7_7") (pintype "passive"))
      (node (ref "U1") (pin "8") (pinfunction "GPIO4/RTC_GPIO4/TOUCH4/ADC1_CH3_8") (pintype "passive"))
    )
    (net (code "28") (name "/GPIO5") (class "Default")
      (node (ref "J1") (pin "8") (pinfunction "8_8") (pintype "passive"))
      (node (ref "U1") (pin "9") (pinfunction "GPIO5/RTC_GPIO5/TOUCH5/ADC1_CH4_9") (pintype "passive"))
    )
    (net (code "29") (name "/GPIO6") (class "Default")
      (node (ref "J1") (pin "9") (pinfunction "9_9") (pintype "passive"))
      (node (ref "U1") (pin "10") (pinfunction "GPIO6/RTC_GPIO6/TOUCH6/ADC1_CH5_10") (pintype "passive"))
    )
    (net (code "30") (name "/GPIO7") (class "Default")
      (node (ref "J1") (pin "10") (pinfunction "10_10") (pintype "passive"))
      (node (ref "U1") (pin "11") (pinfunction "GPIO7/RTC_GPIO7/TOUCH7/ADC1_CH6_11") (pintype "passive"))
    )
    (net (code "31") (name "/GPIO8") (class "Default")
      (node (ref "J1") (pin "11") (pinfunction "11_11") (pintype "passive"))
      (node (ref "U1") (pin "12") (pinfunction "GPIO8/RTC_GPIO8/TOUCH8/ADC1_CH7/SUBSPICS1_12") (pintype "passive"))
    )
    (net (code "32") (name "/GPIO9") (class "Default")
      (node (ref "J1") (pin "12") (pinfunction "12_12") (pintype "passive"))
      (node (ref "U1") (pin "13") (pinfunction "GPIO9/RTC_GPIO9/TOUCH9/ADC1_CH8/FSPIHD/SUBSPIHD_13") (pintype "passive"))
    )
    (net (code "33") (name "/GPIO10") (class "Default")
      (node (ref "J1") (pin "13") (pinfunction "13_13") (pintype "passive"))
      (node (ref "U1") (pin "14") (pinfunction "GPIO10/RTC_GPIO10/TOUCH10/ADC1_CH9/FSPICS0/FSPIIO4/SUBSPICS0_14") (pintype "passive"))
    )
    (net (code "34") (name "/GPIO11") (class "Default")
      (node (ref "J1") (pin "14") (pinfunction "14_14") (pintype "passive"))
      (node (ref "U1") (pin "15") (pinfunction "GPIO11/RTC_GPIO11/TOUCH11/ADC2_CH0/FSPID/FSPIIO5/SUBSPID_15") (pintype "passive"))
    )
    (net (code "35") (name "/GPIO12") (class "Default")
      (node (ref "J1") (pin "15") (pinfunction "15_15") (pintype "passive"))
      (node (ref "U1") (pin "16") (pinfunction "GPIO12/RTC_GPIO12/TOUCH12/ADC2_CH1/FSPICLK/FSPIIO6/SUBSPICLK_16") (pintype "passive"))
    )
    (net (code "36") (name "/GPIO13") (class "Default")
      (node (ref "J1") (pin "16") (pinfunction "16_16") (pintype "passive"))
      (node (ref "U1") (pin "17") (pinfunction "GPIO13/RTC_GPIO13/TOUCH13/ADC2_CH2/FSPIQ/FSPIIO7/SUBSPIQ_17") (pintype "passive"))
    )
    (net (code "37") (name "/GPIO14") (class "Default")
      (node (ref "J1") (pin "17") (pinfunction "17_17") (pintype "passive"))
      (node (ref "U1") (pin "18") (pinfunction "GPIO14/RTC_GPIO14/TOUCH14/ADC2_CH3/FSPIWP/FSPIDQS/SUBSPIWP_18") (pintype "passive"))
    )
    (net (code "38") (name "/GPIO15") (class "Default")
      (node (ref "J1") (pin "18") (pinfunction "18_18") (pintype "passive"))
      (node (ref "U1") (pin "19") (pinfunction "GPIO15/RTC_GPIO15/U0RTS/ADC2_CH4/XTAL_32K_P_19") (pintype "passive"))
    )
    (net (code "39") (name "/GPIO16") (class "Default")
      (node (ref "J1") (pin "19") (pinfunction "19_19") (pintype "passive"))
      (node (ref "U1") (pin "20") (pinfunction "GPIO16/RTC_GPIO16/U0CTS/ADC2_CH5/XTAL_32K_N_20") (pintype "passive"))
    )
    (net (code "40") (name "/GPIO17") (class "Default")
      (node (ref "J1") (pin "20") (pinfunction "20_20") (pintype "passive"))
      (node (ref "U1") (pin "21") (pinfunction "GPIO17/RTC_GPIO17/U1TXD/ADC2_CH6_21") (pintype "passive"))
    )
    (net (code "41") (name "/GPIO18") (class "Default")
      (node (ref "J1") (pin "21") (pinfunction "21_21") (pintype "passive"))
      (node (ref "U1") (pin "22") (pinfunction "GPIO18/RTC_GPIO18/U1RXD/ADC2_CH7/CLK_OUT3_22") (pintype "passive"))
    )
    (net (code "42") (name "/GPIO21") (class "Default")
      (node (ref "J2") (pin "19") (pinfunction "19_19") (pintype "passive"))
      (node (ref "U1") (pin "25") (pinfunction "GPIO21/RTC_GPIO21_25") (pintype "passive"))
    )
    (net (code "43") (name "/GPIO26") (class "Default")
      (node (ref "J2") (pin "18") (pinfunction "18_18") (pintype "passive"))
      (node (ref "U1") (pin "26") (pinfunction "GPIO26/SPICS1_26") (pintype "passive"))
    )
    (net (code "44") (name "/GPIO33") (class "Default")
      (node (ref "J2") (pin "17") (pinfunction "17_17") (pintype "passive"))
      (node (ref "U1") (pin "28") (pinfunction "GPIO33/SPIIO4/FSPIHD/SUBSPIHD_28") (pintype "passive"))
    )
    (net (code "45") (name "/GPIO34") (class "Default")
      (node (ref "J2") (pin "16") (pinfunction "16_16") (pintype "passive"))
      (node (ref "U1") (pin "29") (pinfunction "GPIO34/SPIIO5/FSPICS0/SUBSPICS0_29") (pintype "passive"))
    )
    (net (code "46") (name "/GPIO35") (class "Default")
      (node (ref "J2") (pin "15") (pinfunction "15_15") (pintype "passive"))
      (node (ref "U1") (pin "31") (pinfunction "GPIO35/SPIIO6/FSPID/SUBSPID_31") (pintype "passive"))
    )
    (net (code "47") (name "/GPIO36") (class "Default")
      (node (ref "J2") (pin "14") (pinfunction "14_14") (pintype "passive"))
      (node (ref "U1") (pin "32") (pinfunction "GPIO36/SPIIO7/FSPICLK/SUBSPICLK_32") (pintype "passive"))
    )
    (net (code "48") (name "/GPIO37") (class "Default")
      (node (ref "J2") (pin "13") (pinfunction "13_13") (pintype "passive"))
      (node (ref "U1") (pin "33") (pinfunction "GPIO37/SPIDQS/FSPIQ/SUBSPIQ_33") (pintype "passive"))
    )
    (net (code "49") (name "/GPIO38") (class "Default")
      (node (ref "J2") (pin "12") (pinfunction "12_12") (pintype "passive"))
      (node (ref "U1") (pin "34") (pinfunction "GPIO38/FSPIWP/SUBSPIWP_34") (pintype "passive"))
    )
    (net (code "50") (name "/GPIO39") (class "Default")
      (node (ref "J2") (pin "11") (pinfunction "11_11") (pintype "passive"))
      (node (ref "U1") (pin "35") (pinfunction "MTCK/GPIO39/CLK_OUT3/SUBSPICS1_35") (pintype "passive"))
    )
    (net (code "51") (name "/GPIO40") (class "Default")
      (node (ref "J2") (pin "10") (pinfunction "10_10") (pintype "passive"))
      (node (ref "U1") (pin "36") (pinfunction "MTDO/GPIO40/CLK_OUT2_36") (pintype "passive"))
    )
    (net (code "52") (name "/GPIO41") (class "Default")
      (node (ref "J2") (pin "9") (pinfunction "9_9") (pintype "passive"))
      (node (ref "U1") (pin "37") (pinfunction "MTDI/GPIO41/CLK_OUT1_37") (pintype "passive"))
    )
    (net (code "53") (name "/GPIO42") (class "Default")
      (node (ref "J2") (pin "8") (pinfunction "8_8") (pintype "passive"))
      (node (ref "U1") (pin "38") (pinfunction "MTMS/GPIO42_38") (pintype "passive"))
    )
    (net (code "54") (name "/GPIO45") (class "Default")
      (node (ref "J2") (pin "5") (pinfunction "5_5") (pintype "passive"))
      (node (ref "U1") (pin "41") (pinfunction "GPIO45_41") (pintype "passive"))
    )
    (net (code "55") (name "/GPIO46") (class "Default")
      (node (ref "J2") (pin "4") (pinfunction "4_4") (pintype "passive"))
      (node (ref "U1") (pin "44") (pinfunction "GPIO46_44") (pintype "passive"))
    )
    (net (code "56") (name "/GPIO47") (class "Default")
      (node (ref "J2") (pin "23") (pinfunction "23_23") (pintype "passive"))
      (node (ref "U1") (pin "27") (pinfunction "GPIO47/SPICLK_P_DIFF/SUBSPICLK_P_DIFF_27") (pintype "passive"))
    )
    (net (code "57") (name "/GPIO48") (class "Default")
      (node (ref "J2") (pin "22") (pinfunction "22_22") (pintype "passive"))
      (node (ref "U1") (pin "30") (pinfunction "GPIO48/SPICLK_N_DIFF/SUBSPICLK_N_DIFF_30") (pintype "passive"))
    )
    (net (code "58") (name "/RTS_FTDI") (class "Default")
      (node (ref "Q1") (pin "2") (pinfunction "E_2") (pintype "passive"))
      (node (ref "R22") (pin "2") (pinfunction "2_2") (pintype "passive"))
      (node (ref "U2") (pin "19") (pinfunction "~{RTS}_19") (pintype "passive"))
    )
    (net (code "59") (name "/RXD_FTDI") (class "Default")
      (node (ref "R16") (pin "2") (pinfunction "2_2") (pintype "passive"))
      (node (ref "U2") (pin "1") (pinfunction "RXD_1") (pintype "passive"))
    )
    (net (code "60") (name "/TXD_FTDI") (class "Default")
      (node (ref "R18") (pin "2") (pinfunction "2_2") (pintype "passive"))
      (node (ref "U2") (pin "17") (pinfunction "TXD_17") (pintype "passive"))
    )
    (net (code "61") (name "/U0RXD") (class "Default")
      (node (ref "J2") (pin "6") (pinfunction "6_6") (pintype "passive"))
      (node (ref "R18") (pin "1") (pinfunction "1_1") (pintype "passive"))
      (node (ref "U1") (pin "40") (pinfunction "U0RXD/GPIO44/CLK_OUT2_40") (pintype "passive"))
    )
    (net (code "62") (name "/U0TXD") (class "Default")
      (node (ref "J2") (pin "7") (pinfunction "7_7") (pintype "passive"))
      (node (ref "R16") (pin "1") (pinfunction "1_1") (pintype "passive"))
      (node (ref "U1") (pin "39") (pinfunction "U0TXD/GPIO43/CLK_OUT1_39") (pintype "passive"))
    )
    (net (code "63") (name "/VBUS_SENSE") (class "Default")
      (node (ref "R10") (pin "1") (pinfunction "1_1") (pintype "passive"))
      (node (ref "R13") (pin "2") (pinfunction "2_2") (pintype "passive"))
      (node (ref "U2") (pin "16") (pinfunction "CBUS3_16") (pintype "passive"))
    )
    (net (code "64") (name "GND") (class "Default")
      (node (ref "C1") (pin "1") (pinfunction "1_1") (pintype "passive"))
      (node (ref "C10") (pin "1") (pinfunction "1_1") (pintype "passive"))
      (node (ref "C11") (pin "1") (pinfunction "1_1") (pintype "passive"))
      (node (ref "C12") (pin "1") (pinfunction "1_1") (pintype "passive"))
      (node (ref "C13") (pin "1") (pinfunction "1_1") (pintype "passive"))
      (node (ref "C14") (pin "1") (pinfunction "1_1") (pintype "passive"))
      (node (ref "C15") (pin "1") (pinfunction "1_1") (pintype "passive"))
      (node (ref "C16") (pin "1") (pinfunction "1_1") (pintype "passive"))
      (node (ref "C17") (pin "1") (pinfunction "1_1") (pintype "passive"))
      (node (ref "C2") (pin "1") (pinfunction "1_1") (pintype "passive"))
      (node (ref "C3") (pin "1") (pinfunction "1_1") (pintype "passive"))
      (node (ref "C4") (pin "1") (pinfunction "1_1") (pintype "passive"))
      (node (ref "C5") (pin "1") (pinfunction "1_1") (pintype "passive"))
      (node (ref "C6") (pin "1") (pinfunction "1_1") (pintype "passive"))
      (node (ref "C7") (pin "1") (pinfunction "1_1") (pintype "passive"))
      (node (ref "C8") (pin "1") (pinfunction "1_1") (pintype "passive"))
      (node (ref "C9") (pin "1") (pinfunction "1_1") (pintype "passive"))
      (node (ref "D1") (pin "1") (pinfunction "1_1") (pintype "passive"))
      (node (ref "D3") (pin "2") (pinfunction "2_2") (pintype "passive"))
      (node (ref "D4") (pin "2") (pinfunction "2_2") (pintype "passive"))
      (node (ref "D5") (pin "2") (pinfunction "2_2") (pintype "passive"))
      (node (ref "D6") (pin "2") (pinfunction "2_2") (pintype "passive"))
      (node (ref "D7") (pin "2") (pinfunction "2_2") (pintype "passive"))
      (node (ref "D8") (pin "2") (pinfunction "2_2") (pintype "passive"))
      (node (ref "J1") (pin "1") (pinfunction "1_1") (pintype "passive"))
      (node (ref "J1") (pin "23") (pinfunction "23_23") (pintype "passive"))
      (node (ref "J2") (pin "2") (pinfunction "2_2") (pintype "passive"))
      (node (ref "J2") (pin "24") (pinfunction "24_24") (pintype "passive"))
      (node (ref "R11") (pin "1") (pinfunction "1_1") (pintype "passive"))
      (node (ref "R12") (pin "1") (pinfunction "1_1") (pintype "passive"))
      (node (ref "R13") (pin "1") (pinfunction "1_1") (pintype "passive"))
      (node (ref "R14") (pin "1") (pinfunction "1_1") (pintype "passive"))
      (node (ref "R15") (pin "1") (pinfunction "1_1") (pintype "passive"))
      (node (ref "R9") (pin "1") (pinfunction "1_1") (pintype "passive"))
      (node (ref "SW2") (pin "3") (pinfunction "3_3") (pintype "passive"))
      (node (ref "SW2") (pin "4") (pinfunction "4_4") (pintype "passive"))
      (node (ref "U1") (pin "1") (pinfunction "GND_01_1") (pintype "passive"))
      (node (ref "U1") (pin "2") (pinfunction "GND_02_2") (pintype "passive"))
      (node (ref "U1") (pin "42") (pinfunction "GND_42") (pintype "passive"))
      (node (ref "U1") (pin "43") (pinfunction "GND_43") (pintype "passive"))
      (node (ref "U1") (pin "46") (pinfunction "GND_46_46") (pintype "passive"))
      (node (ref "U1") (pin "47") (pinfunction "GND_47_47") (pintype "passive"))
      (node (ref "U1") (pin "48") (pinfunction "GND_48_48") (pintype "passive"))
      (node (ref "U1") (pin "49") (pinfunction "GND_49_49") (pintype "passive"))
      (node (ref "U1") (pin "50") (pinfunction "GND_50_50") (pintype "passive"))
      (node (ref "U1") (pin "51") (pinfunction "GND_51_51") (pintype "passive"))
      (node (ref "U1") (pin "52") (pinfunction "GND_52_52") (pintype "passive"))
      (node (ref "U1") (pin "53") (pinfunction "GND_53_53") (pintype "passive"))
      (node (ref "U1") (pin "54") (pinfunction "GND_54_54") (pintype "passive"))
      (node (ref "U1") (pin "55") (pinfunction "GND_55_55") (pintype "passive"))
      (node (ref "U1") (pin "56") (pinfunction "GND_56_56") (pintype "passive"))
      (node (ref "U1") (pin "57") (pinfunction "GND_57_57") (pintype "passive"))
      (node (ref "U1") (pin "58") (pinfunction "GND_58_58") (pintype "passive"))
      (node (ref "U1") (pin "59") (pinfunction "GND_59_59") (pintype "passive"))
      (node (ref "U1") (pin "60") (pinfunction "GND_60_60") (pintype "passive"))
      (node (ref "U1") (pin "61") (pinfunction "GND_61_61") (pintype "passive"))
      (node (ref "U1") (pin "62") (pinfunction "GND_62_62") (pintype "passive"))
      (node (ref "U1") (pin "63") (pinfunction "GND_63_63") (pintype "passive"))
      (node (ref "U1") (pin "64") (pinfunction "GND_64_64") (pintype "passive"))
      (node (ref "U1") (pin "65") (pinfunction "GND_65_65") (pintype "passive"))
      (node (ref "U1") (pin "66") (pinfunction "GND_66_66") (pintype "passive"))
      (node (ref "U1") (pin "67") (pinfunction "GND_67_67") (pintype "passive"))
      (node (ref "U1") (pin "68") (pinfunction "GND_68_68") (pintype "passive"))
      (node (ref "U1") (pin "69") (pinfunction "GND_69_69") (pintype "passive"))
      (node (ref "U1") (pin "70") (pinfunction "GND_70_70") (pintype "passive"))
      (node (ref "U1") (pin "71") (pinfunction "GND_71_71") (pintype "passive"))
      (node (ref "U1") (pin "72") (pinfunction "GND_72_72") (pintype "passive"))
      (node (ref "U1") (pin "73") (pinfunction "GND_73_73") (pintype "passive"))
      (node (ref "U2") (pin "13") (pinfunction "GND_13") (pintype "passive"))
      (node (ref "U2") (pin "21") (pinfunction "GND_21") (pintype "passive"))
      (node (ref "U2") (pin "3") (pinfunction "GND_3") (pintype "passive"))
      (node (ref "U3") (pin "2") (pinfunction "GND_2") (pintype "power_in"))
      (node (ref "U3") (pin "4") (pinfunction "GND_4") (pintype "power_in"))
    )
    (net (code "65") (name "Net-(D1-Pad2)") (class "Default")
      (node (ref "D1") (pin "2") (pinfunction "2_2") (pintype "passive"))
      (node (ref "R2") (pin "1") (pinfunction "1_1") (pintype "passive"))
    )
    (net (code "66") (name "Net-(D2-Pad2)") (class "Default")
      (node (ref "D2") (pin "2") (pinfunction "2_2") (pintype "passive"))
      (node (ref "R3") (pin "1") (pinfunction "1_1") (pintype "passive"))
    )
    (net (code "67") (name "Net-(J3-CC1)") (class "Default")
      (node (ref "J3") (pin "A5") (pinfunction "CC1_A5") (pintype "passive"))
      (node (ref "R12") (pin "2") (pinfunction "2_2") (pintype "passive"))
    )
    (net (code "68") (name "Net-(J3-CC2)") (class "Default")
      (node (ref "J3") (pin "B5") (pinfunction "CC2_B5") (pintype "passive"))
      (node (ref "R11") (pin "2") (pinfunction "2_2") (pintype "passive"))
    )
    (net (code "69") (name "Net-(J4-CC1)") (class "Default")
      (node (ref "J4") (pin "A5") (pinfunction "CC1_A5") (pintype "passive"))
      (node (ref "R15") (pin "2") (pinfunction "2_2") (pintype "passive"))
    )
    (net (code "70") (name "Net-(J4-CC2)") (class "Default")
      (node (ref "J4") (pin "B5") (pinfunction "CC2_B5") (pintype "passive"))
      (node (ref "R14") (pin "2") (pinfunction "2_2") (pintype "passive"))
    )
    (net (code "71") (name "Net-(Q1-B)") (class "Default")
      (node (ref "Q1") (pin "1") (pinfunction "B_1") (pintype "passive"))
      (node (ref "R21") (pin "1") (pinfunction "1_1") (pintype "passive"))
    )
    (net (code "72") (name "Net-(Q2-B)") (class "Default")
      (node (ref "Q2") (pin "1") (pinfunction "B_1") (pintype "passive"))
      (node (ref "R22") (pin "1") (pinfunction "1_1") (pintype "passive"))
    )
    (net (code "73") (name "Net-(U2-CBUS0)") (class "Default")
      (node (ref "R9") (pin "2") (pinfunction "2_2") (pintype "passive"))
      (node (ref "U2") (pin "15") (pinfunction "CBUS0_15") (pintype "passive"))
    )
    (net (code "74") (name "TYPECGND") (class "Default")
      (node (ref "J3") (pin "A1B12") (pinfunction "GND_A1B12_A1B12") (pintype "passive"))
      (node (ref "J3") (pin "B1A12") (pinfunction "GND_B1A12_B1A12") (pintype "passive"))
      (node (ref "J3") (pin "S1") (pinfunction "SHIELD_1_S1") (pintype "passive"))
      (node (ref "J3") (pin "S2") (pinfunction "SHIELD_2_S2") (pintype "passive"))
      (node (ref "J3") (pin "S3") (pinfunction "SHIELD_3_S3") (pintype "passive"))
      (node (ref "J3") (pin "S4") (pinfunction "SHIELD_4_S4") (pintype "passive"))
      (node (ref "J4") (pin "A1B12") (pinfunction "GND_A1B12_A1B12") (pintype "passive"))
      (node (ref "J4") (pin "B1A12") (pinfunction "GND_B1A12_B1A12") (pintype "passive"))
      (node (ref "J4") (pin "S1") (pinfunction "SHIELD_1_S1") (pintype "passive"))
      (node (ref "J4") (pin "S2") (pinfunction "SHIELD_2_S2") (pintype "passive"))
      (node (ref "J4") (pin "S3") (pinfunction "SHIELD_3_S3") (pintype "passive"))
      (node (ref "J4") (pin "S4") (pinfunction "SHIELD_4_S4") (pintype "passive"))
      (node (ref "SW1") (pin "3") (pinfunction "3_3") (pintype "passive"))
      (node (ref "SW1") (pin "4") (pinfunction "4_4") (pintype "passive"))
    )
    (net (code "75") (name "unconnected-(J1-Pad24)") (class "Default")
      (node (ref "J1") (pin "24") (pinfunction "24_24") (pintype "passive+no_connect"))
    )
    (net (code "76") (name "unconnected-(J3-SBU1-PadA8)") (class "Default")
      (node (ref "J3") (pin "A8") (pinfunction "SBU1_A8") (pintype "passive+no_connect"))
    )
    (net (code "77") (name "unconnected-(J3-SBU2-PadB8)") (class "Default")
      (node (ref "J3") (pin "B8") (pinfunction "SBU2_B8") (pintype "passive+no_connect"))
    )
    (net (code "78") (name "unconnected-(J4-SBU1-PadA8)") (class "Default")
      (node (ref "J4") (pin "A8") (pinfunction "SBU1_A8") (pintype "passive+no_connect"))
    )
    (net (code "79") (name "unconnected-(J4-SBU2-PadB8)") (class "Default")
      (node (ref "J4") (pin "B8") (pinfunction "SBU2_B8") (pintype "passive+no_connect"))
    )
    (net (code "80") (name "unconnected-(U2-CBUS1-Pad14)") (class "Default")
      (node (ref "U2") (pin "14") (pinfunction "CBUS1_14") (pintype "passive+no_connect"))
    )
    (net (code "81") (name "unconnected-(U2-CBUS2-Pad7)") (class "Default")
      (node (ref "U2") (pin "7") (pinfunction "CBUS2_7") (pintype "passive+no_connect"))
    )
    (net (code "82") (name "unconnected-(U2-~{CTS}-Pad6)") (class "Default")
      (node (ref "U2") (pin "6") (pinfunction "~{CTS}_6") (pintype "passive+no_connect"))
    )
    (net (code "83") (name "unconnected-(U2-~{DCD}-Pad5)") (class "Default")
      (node (ref "U2") (pin "5") (pinfunction "~{DCD}_5") (pintype "passive+no_connect"))
    )
    (net (code "84") (name "unconnected-(U2-~{DSR}-Pad4)") (class "Default")
      (node (ref "U2") (pin "4") (pinfunction "~{DSR}_4") (pintype "passive+no_connect"))
    )
    (net (code "85") (name "unconnected-(U2-~{RI}-Pad2)") (class "Default")
      (node (ref "U2") (pin "2") (pinfunction "~{RI}_2") (pintype "passive+no_connect"))
    )
  )
)
